# IR_Transmitter.net
KiCad netlist of a schematic drawn in EAGLE
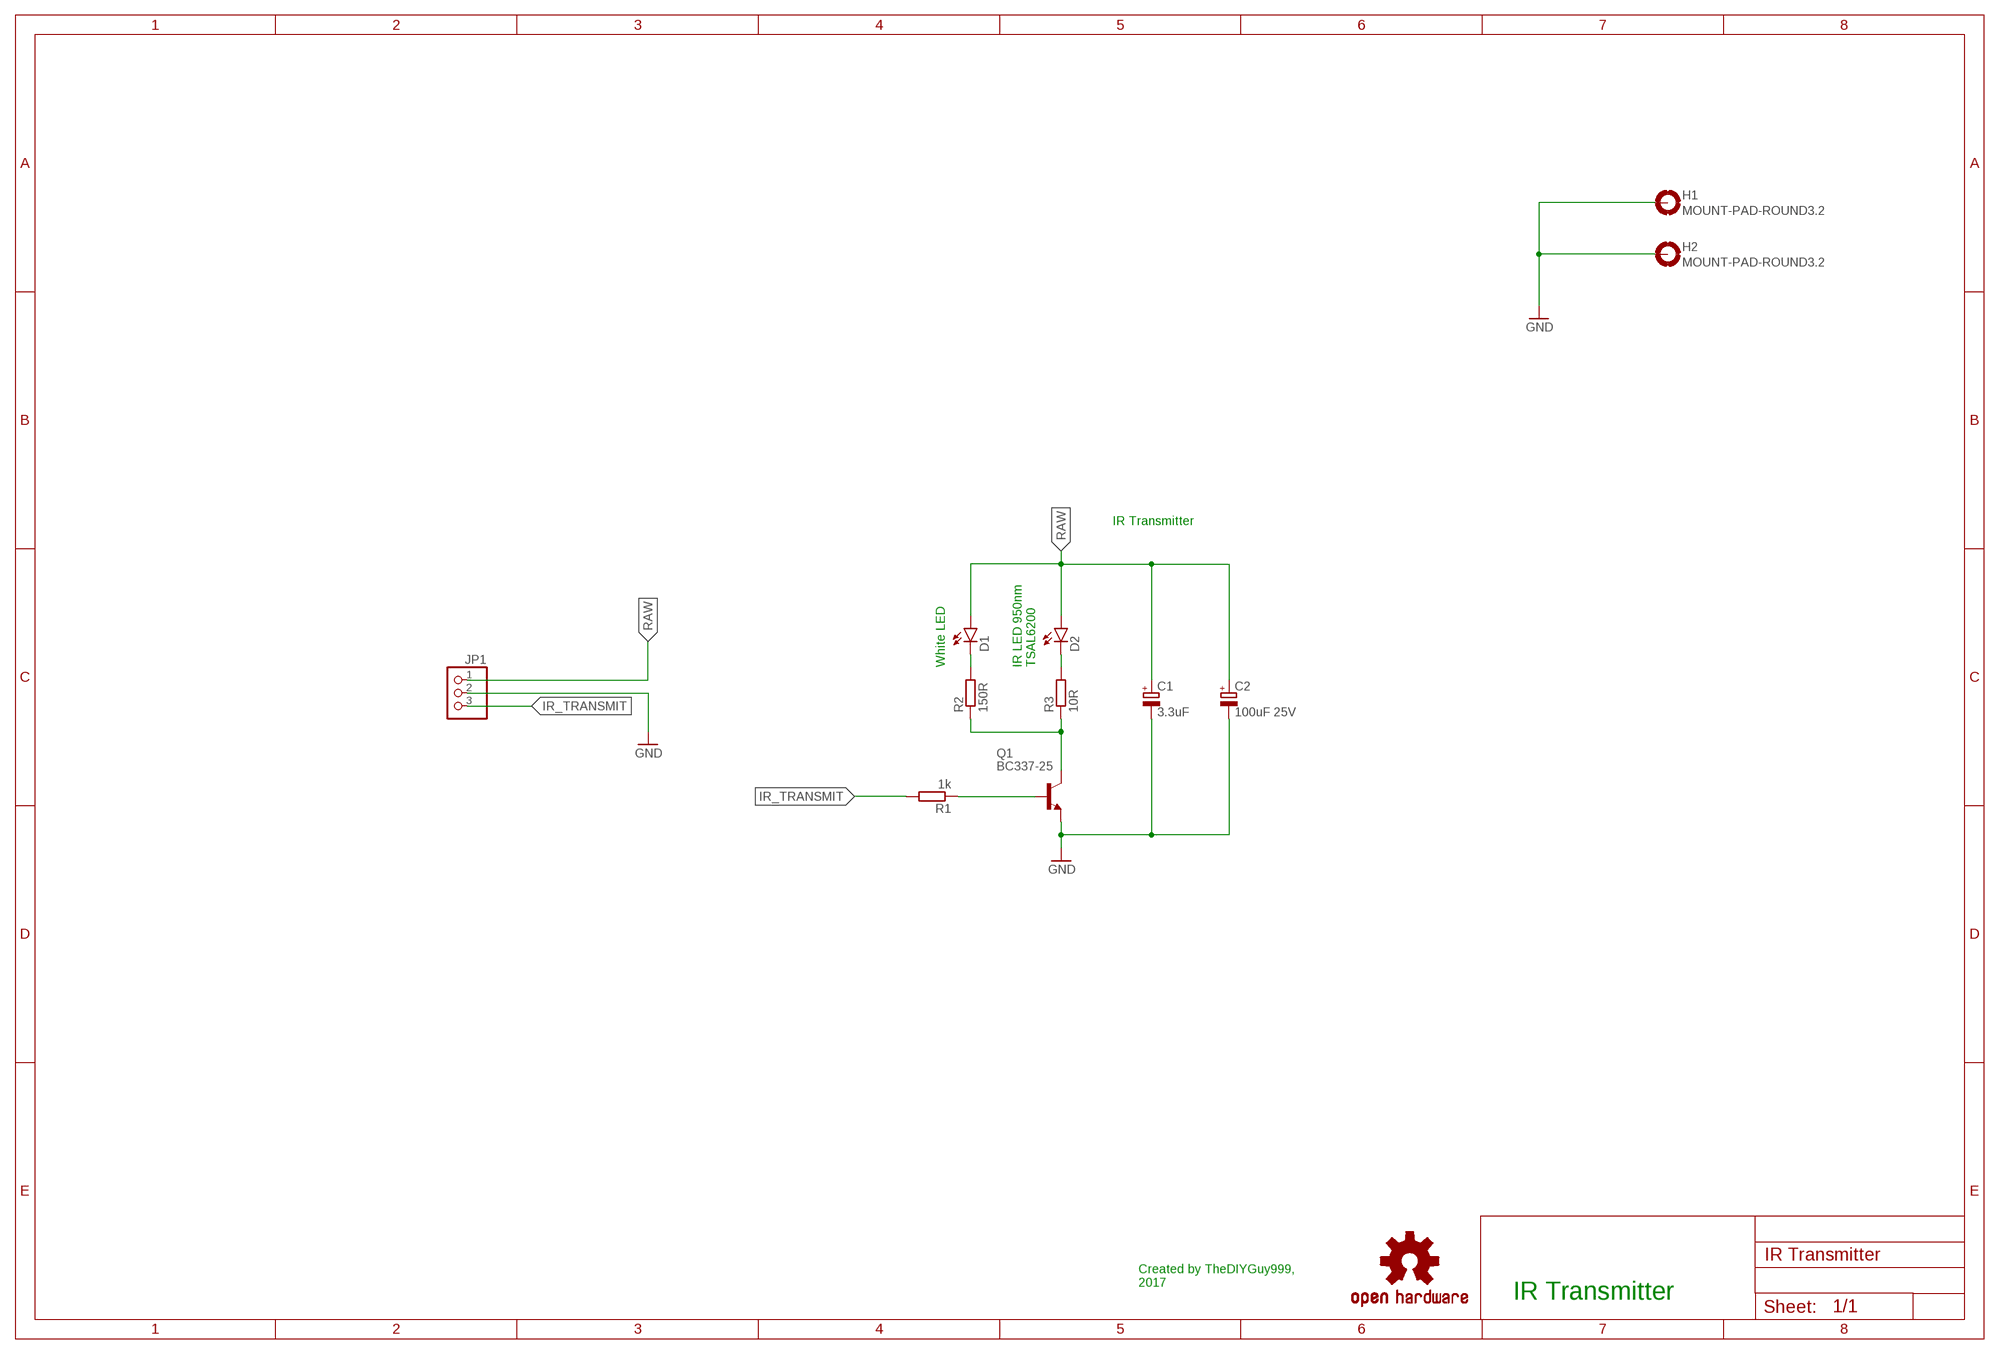
[diagram p0: schematic, sheet 1]

(export (version "E")
  (design (tool "Eeschema 10.0.6"))
  (components
    (comp (ref "C1")
      (value "3.3uF")
      (footprint "eagle-import:B45181A")
      (libsource (lib "eagle-import") (part "CPOL-EUB45181A"))
    )
    (comp (ref "C2")
      (value "100uF 25V")
      (footprint "eagle-import:E2,5-7")
      (libsource (lib "eagle-import") (part "CPOL-EUE2.5-7"))
    )
    (comp (ref "D1")
      (value "LED5MM")
      (footprint "eagle-import:LED5MM")
      (libsource (lib "eagle-import") (part "LED5MM"))
    )
    (comp (ref "D2")
      (value "LED5MM")
      (footprint "eagle-import:LED5MM")
      (libsource (lib "eagle-import") (part "LED5MM"))
    )
    (comp (ref "H1")
      (value "MOUNT-PAD-ROUND3.2")
      (footprint "eagle-import:3,2-PAD")
      (libsource (lib "eagle-import") (part "MOUNT-PAD-ROUND3.2"))
    )
    (comp (ref "H2")
      (value "MOUNT-PAD-ROUND3.2")
      (footprint "eagle-import:3,2-PAD")
      (libsource (lib "eagle-import") (part "MOUNT-PAD-ROUND3.2"))
    )
    (comp (ref "JP1")
      (value "PINHD-1X3")
      (footprint "eagle-import:1X03")
      (libsource (lib "eagle-import") (part "PINHD-1X3"))
    )
    (comp (ref "LOGO1")
      (value "OSHW-LOGOM")
      (footprint "eagle-import:OSHW-LOGO-M")
      (libsource (lib "eagle-import") (part "OSHW-LOGOM"))
    )
    (comp (ref "Q1")
      (value "BC337-25")
      (footprint "eagle-import:TO92")
      (libsource (lib "eagle-import") (part "BC337-25"))
    )
    (comp (ref "R1")
      (value "1k")
      (footprint "eagle-import:0207_2V")
      (libsource (lib "eagle-import") (part "R-EU_0207/2V"))
    )
    (comp (ref "R2")
      (value "150R")
      (footprint "eagle-import:0207_2V")
      (libsource (lib "eagle-import") (part "R-EU_0207/2V"))
    )
    (comp (ref "R3")
      (value "10R")
      (footprint "eagle-import:0207_2V")
      (libsource (lib "eagle-import") (part "R-EU_0207/2V"))
    )
  )
  (nets
    (net (code "1") (name "GND") (class "Default")
      (node (ref "C1") (pin "-") (pinfunction "-_-") (pintype "passive"))
      (node (ref "C2") (pin "-") (pinfunction "-_-") (pintype "passive"))
      (node (ref "H1") (pin "B3,2") (pinfunction "MOUNT_B3,2") (pintype "passive"))
      (node (ref "H2") (pin "B3,2") (pinfunction "MOUNT_B3,2") (pintype "passive"))
      (node (ref "JP1") (pin "2") (pinfunction "2_2") (pintype "passive"))
      (node (ref "Q1") (pin "1") (pinfunction "E_1") (pintype "passive"))
    )
    (net (code "2") (name "IR_TRANSMIT") (class "Default")
      (node (ref "JP1") (pin "3") (pinfunction "3_3") (pintype "passive"))
      (node (ref "R1") (pin "2") (pinfunction "2_2") (pintype "passive"))
    )
    (net (code "3") (name "Net-(D1-C)") (class "Default")
      (node (ref "D1") (pin "K") (pinfunction "C_K") (pintype "passive"))
      (node (ref "R2") (pin "2") (pinfunction "2_2") (pintype "passive"))
    )
    (net (code "4") (name "Net-(D2-C)") (class "Default")
      (node (ref "D2") (pin "K") (pinfunction "C_K") (pintype "passive"))
      (node (ref "R3") (pin "2") (pinfunction "2_2") (pintype "passive"))
    )
    (net (code "5") (name "Net-(Q1-B)") (class "Default")
      (node (ref "Q1") (pin "2") (pinfunction "B_2") (pintype "passive"))
      (node (ref "R1") (pin "1") (pinfunction "1_1") (pintype "passive"))
    )
    (net (code "6") (name "Net-(Q1-C)") (class "Default")
      (node (ref "Q1") (pin "3") (pinfunction "C_3") (pintype "passive"))
      (node (ref "R2") (pin "1") (pinfunction "1_1") (pintype "passive"))
      (node (ref "R3") (pin "1") (pinfunction "1_1") (pintype "passive"))
    )
    (net (code "7") (name "RAW") (class "Default")
      (node (ref "C1") (pin "+") (pinfunction "+_+") (pintype "passive"))
      (node (ref "C2") (pin "+") (pinfunction "+_+") (pintype "passive"))
      (node (ref "D1") (pin "A") (pinfunction "A_A") (pintype "passive"))
      (node (ref "D2") (pin "A") (pinfunction "A_A") (pintype "passive"))
      (node (ref "JP1") (pin "1") (pinfunction "1_1") (pintype "passive"))
    )
  )
)
